# hello_echo_Arpi_02.net
KiCad netlist of a schematic drawn in EAGLE
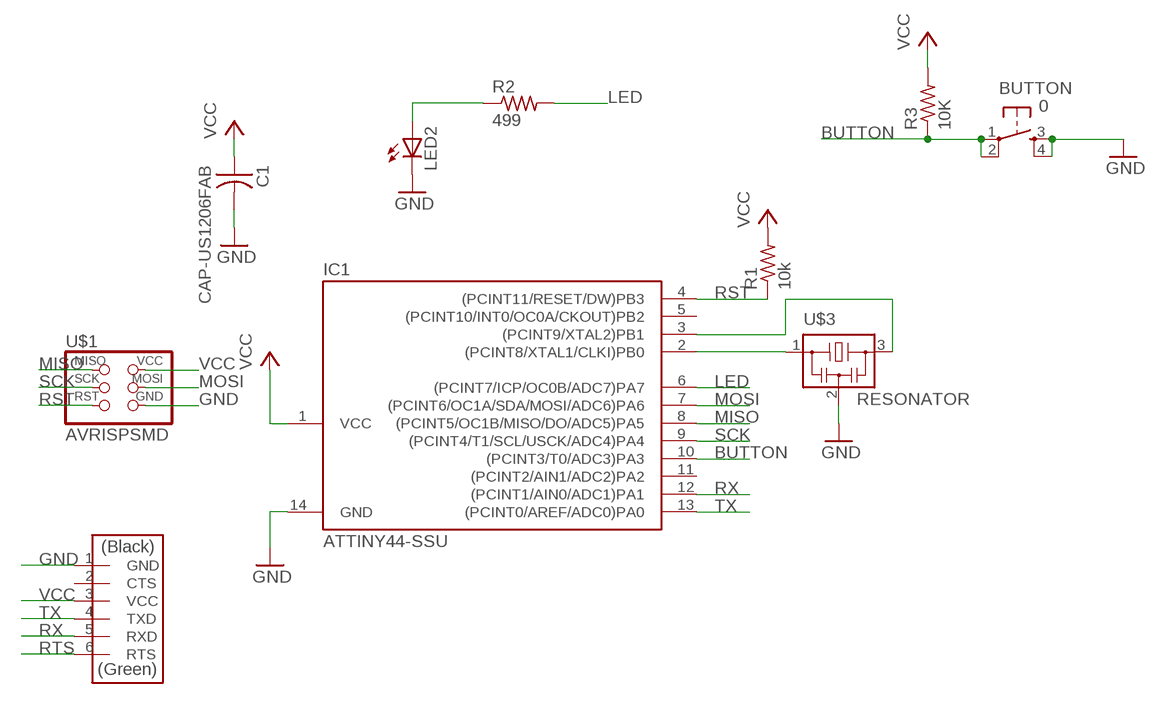
[diagram p0: schematic, sheet 1]

(export (version "E")
  (design (tool "Eeschema 10.0.6"))
  (components
    (comp (ref "BUTTON")
      (value "0")
      (footprint "eagle-import:6MM_SWITCH")
      (libsource (lib "eagle-import") (part "6MM_SWITCH6MM_SWITCH"))
    )
    (comp (ref "C1")
      (value "CAP-US1206FAB")
      (footprint "eagle-import:C1206FAB")
      (libsource (lib "eagle-import") (part "CAP-US1206FAB"))
    )
    (comp (ref "IC1")
      (value "ATTINY44-SSU")
      (footprint "eagle-import:SOIC14")
      (libsource (lib "eagle-import") (part "ATTINY44-SSU"))
    )
    (comp (ref "LED2")
      (value "LEDKA-3528ASYC")
      (footprint "eagle-import:KA-3528ASYC")
      (libsource (lib "eagle-import") (part "LEDKA-3528ASYC"))
    )
    (comp (ref "R1")
      (value "10k")
      (footprint "eagle-import:R1206FAB")
      (libsource (lib "eagle-import") (part "RES-US1206FAB"))
    )
    (comp (ref "R2")
      (value "499")
      (footprint "eagle-import:R1206FAB")
      (libsource (lib "eagle-import") (part "RES-US1206FAB"))
    )
    (comp (ref "R3")
      (value "10K")
      (footprint "eagle-import:R1206FAB")
      (libsource (lib "eagle-import") (part "RES-US1206FAB"))
    )
    (comp (ref "U$1")
      (value "AVRISPSMD")
      (footprint "eagle-import:2X03SMD")
      (libsource (lib "eagle-import") (part "AVRISPSMD"))
    )
    (comp (ref "U$2")
      (value "FTDI-SMD-HEADER")
      (footprint "eagle-import:1X06SMD")
      (libsource (lib "eagle-import") (part "FTDI-SMD-HEADER"))
    )
    (comp (ref "U$3")
      (value "RESONATOR")
      (footprint "eagle-import:EFOBM")
      (libsource (lib "eagle-import") (part "RESONATOR"))
    )
  )
  (nets
    (net (code "1") (name "/BUTTON") (class "Default")
      (node (ref "BUTTON") (pin "1") (pinfunction "P_1") (pintype "passive"))
      (node (ref "BUTTON") (pin "2") (pinfunction "P1_2") (pintype "passive"))
      (node (ref "IC1") (pin "10") (pinfunction "(PCINT3/T0/ADC3)PA3_10") (pintype "bidirectional"))
      (node (ref "R3") (pin "1") (pinfunction "1_1") (pintype "passive"))
    )
    (net (code "2") (name "/LED") (class "Default")
      (node (ref "IC1") (pin "6") (pinfunction "(PCINT7/ICP/OC0B/ADC7)PA7_6") (pintype "bidirectional"))
      (node (ref "R2") (pin "2") (pinfunction "2_2") (pintype "passive"))
    )
    (net (code "3") (name "/MISO") (class "Default")
      (node (ref "IC1") (pin "8") (pinfunction "(PCINT5/OC1B/MISO/DO/ADC5)PA5_8") (pintype "bidirectional"))
      (node (ref "U$1") (pin "1") (pinfunction "MISO_1") (pintype "passive"))
    )
    (net (code "4") (name "/MOSI") (class "Default")
      (node (ref "IC1") (pin "7") (pinfunction "(PCINT6/OC1A/SDA/MOSI/ADC6)PA6_7") (pintype "bidirectional"))
      (node (ref "U$1") (pin "4") (pinfunction "MOSI_4") (pintype "passive"))
    )
    (net (code "5") (name "/RST") (class "Default")
      (node (ref "IC1") (pin "4") (pinfunction "(PCINT11/RESET/DW)PB3_4") (pintype "bidirectional"))
      (node (ref "R1") (pin "1") (pinfunction "1_1") (pintype "passive"))
      (node (ref "U$1") (pin "5") (pinfunction "RST_5") (pintype "passive"))
    )
    (net (code "6") (name "/RTS") (class "Default")
      (node (ref "U$2") (pin "6") (pinfunction "RTS_6") (pintype "bidirectional"))
    )
    (net (code "7") (name "/RX") (class "Default")
      (node (ref "IC1") (pin "12") (pinfunction "(PCINT1/AIN0/ADC1)PA1_12") (pintype "bidirectional"))
      (node (ref "U$2") (pin "5") (pinfunction "RXD_5") (pintype "bidirectional"))
    )
    (net (code "8") (name "/SCK") (class "Default")
      (node (ref "IC1") (pin "9") (pinfunction "(PCINT4/T1/SCL/USCK/ADC4)PA4_9") (pintype "bidirectional"))
      (node (ref "U$1") (pin "3") (pinfunction "SCK_3") (pintype "passive"))
    )
    (net (code "9") (name "/TX") (class "Default")
      (node (ref "IC1") (pin "13") (pinfunction "(PCINT0/AREF/ADC0)PA0_13") (pintype "bidirectional"))
      (node (ref "U$2") (pin "4") (pinfunction "TXD_4") (pintype "bidirectional"))
    )
    (net (code "10") (name "GND") (class "Default")
      (node (ref "BUTTON") (pin "3") (pinfunction "S_3") (pintype "passive"))
      (node (ref "BUTTON") (pin "4") (pinfunction "S1_4") (pintype "passive"))
      (node (ref "C1") (pin "2") (pinfunction "2_2") (pintype "passive"))
      (node (ref "IC1") (pin "14") (pinfunction "GND_14") (pintype "power_in"))
      (node (ref "LED2") (pin "C") (pinfunction "C_C") (pintype "passive"))
      (node (ref "U$1") (pin "6") (pinfunction "GND_6") (pintype "passive"))
      (node (ref "U$2") (pin "1") (pinfunction "GND_1") (pintype "bidirectional"))
      (node (ref "U$3") (pin "2") (pinfunction "2_2") (pintype "passive"))
    )
    (net (code "11") (name "Net-(IC1-(PCINT8{slash}XTAL1{slash}CLKI)PB0)") (class "Default")
      (node (ref "IC1") (pin "2") (pinfunction "(PCINT8/XTAL1/CLKI)PB0_2") (pintype "bidirectional"))
      (node (ref "U$3") (pin "1") (pinfunction "1_1") (pintype "passive"))
    )
    (net (code "12") (name "Net-(IC1-(PCINT9{slash}XTAL2)PB1)") (class "Default")
      (node (ref "IC1") (pin "3") (pinfunction "(PCINT9/XTAL2)PB1_3") (pintype "bidirectional"))
      (node (ref "U$3") (pin "3") (pinfunction "3_3") (pintype "passive"))
    )
    (net (code "13") (name "Net-(LED2-PadA)") (class "Default")
      (node (ref "LED2") (pin "A") (pinfunction "A_A") (pintype "passive"))
      (node (ref "R2") (pin "1") (pinfunction "1_1") (pintype "passive"))
    )
    (net (code "14") (name "VCC") (class "Default")
      (node (ref "C1") (pin "1") (pinfunction "1_1") (pintype "passive"))
      (node (ref "IC1") (pin "1") (pinfunction "VCC_1") (pintype "power_in"))
      (node (ref "R1") (pin "2") (pinfunction "2_2") (pintype "passive"))
      (node (ref "R3") (pin "2") (pinfunction "2_2") (pintype "passive"))
      (node (ref "U$1") (pin "2") (pinfunction "VCC_2") (pintype "passive"))
      (node (ref "U$2") (pin "3") (pinfunction "VCC_3") (pintype "bidirectional"))
    )
    (net (code "15") (name "unconnected-(IC1-(PCINT2{slash}AIN1{slash}ADC2)PA2-Pad11)") (class "Default")
      (node (ref "IC1") (pin "11") (pinfunction "(PCINT2/AIN1/ADC2)PA2_11") (pintype "bidirectional"))
    )
    (net (code "16") (name "unconnected-(IC1-(PCINT10{slash}INT0{slash}OC0A{slash}CKOUT)PB2-Pad5)") (class "Default")
      (node (ref "IC1") (pin "5") (pinfunction "(PCINT10/INT0/OC0A/CKOUT)PB2_5") (pintype "bidirectional"))
    )
    (net (code "17") (name "unconnected-(U$2-CTS-Pad2)") (class "Default")
      (node (ref "U$2") (pin "2") (pinfunction "CTS_2") (pintype "bidirectional"))
    )
  )
)
